# MIXR_Processing_-_STM32_NOR_Flash.net
KiCad netlist of a schematic drawn in Altium Designer
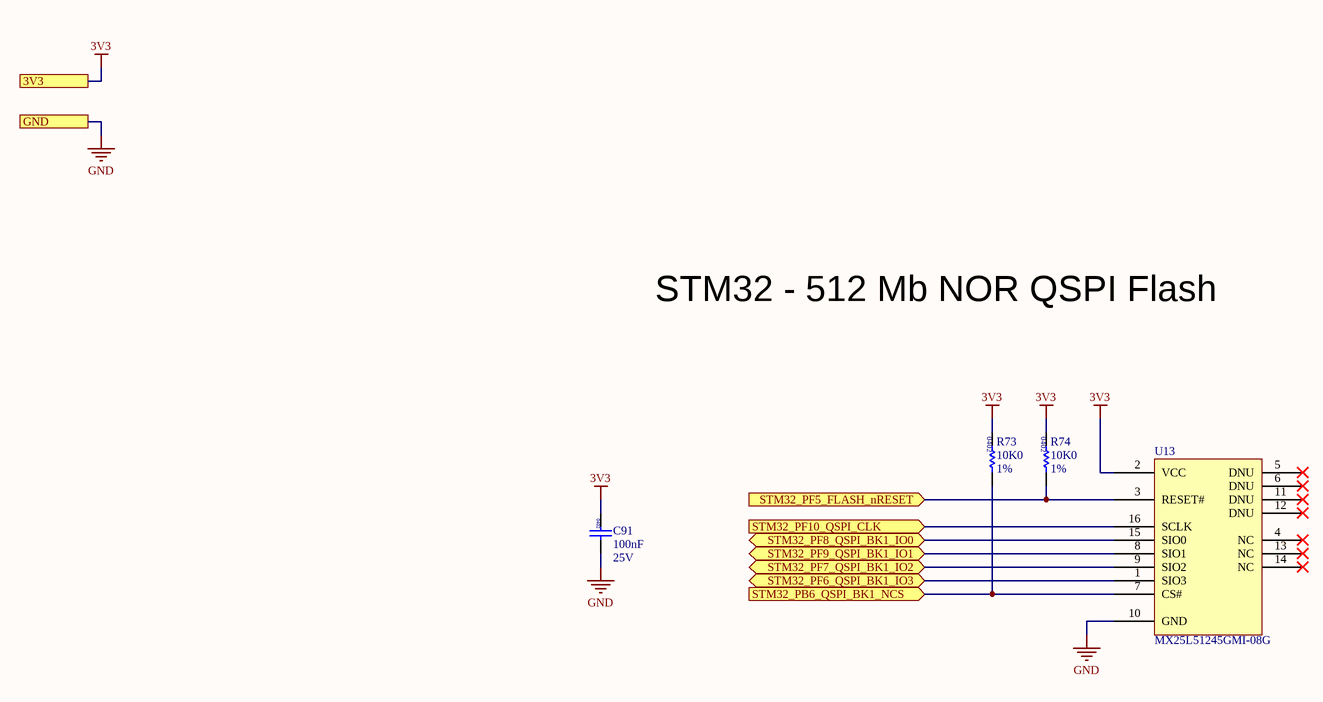
[diagram p0: MIXR Processing - STM32 NOR Flash.SchDoc]

(export (version "E")
  (design (tool "Eeschema 10.0.6"))
  (components
    (comp (ref "C91")
      (value "CAP CER 0.1UF 16V X7R 0402")
      (footprint "CAP 0402")
      (description "Cap Ceramic 0.1uF 25V X7R 10% SMD 0402 125C Paper T/R")
      (fields
        (field (name "TOLERANCE") "10%")
        (field (name "CAPACITANCE") "100nF")
        (field (name "VOLTAGE") "25V")
        (field (name "MANUFACTURER") "Murata")
      )
      (libsource (lib "Schematic Diagrams") (part "CAP CER 0.1UF 16V X7R 0402"))
    )
    (comp (ref "R73")
      (value "RES 10K OHM 1% 1/16W 0402")
      (footprint "RES 0402")
      (description "Surface Mount Thick Film Resistor, Rc Series, 10 Kohm, 62.5 Mw, - 1%, 50 V, 0402 [1005 Metric]")
      (fields
        (field (name "MANUFACTURER") "Yageo")
        (field (name "MANUFACTURER PART NUMBER") "RC0402FR-0710KL")
        (field (name "RESISTANCE") "10K0")
        (field (name "TOLERANCE") "1%")
      )
      (libsource (lib "Schematic Diagrams") (part "RES 10K OHM 1% 1/16W 0402"))
    )
    (comp (ref "R74")
      (value "RES 10K OHM 1% 1/16W 0402")
      (footprint "RES 0402")
      (description "Surface Mount Thick Film Resistor, Rc Series, 10 Kohm, 62.5 Mw, - 1%, 50 V, 0402 [1005 Metric]")
      (fields
        (field (name "MANUFACTURER") "Yageo")
        (field (name "MANUFACTURER PART NUMBER") "RC0402FR-0710KL")
        (field (name "RESISTANCE") "10K0")
        (field (name "TOLERANCE") "1%")
      )
      (libsource (lib "Schematic Diagrams") (part "RES 10K OHM 1% 1/16W 0402"))
    )
    (comp (ref "U13")
      (value "IC FLASH NOR 512Mb SPI 166MHz 16-SOP")
      (footprint "SOP127P1030X265-16N")
      (description "FLASH - NOR Memory IC 512Mb (64M x 8) SPI 166MHz 16-SOP")
      (fields
        (field (name "MANUFACTURER") "Macronix")
        (field (name "MANUFACTURER PART NUMBER") "MX25L51245GMI-08G")
      )
      (libsource (lib "Schematic Diagrams") (part "IC FLASH NOR 512Mb SPI 166MHz 16-SOP"))
    )
  )
  (nets
    (net (code "1") (name "/STM32_PB6_QSPI_BK1_NCS") (class "Default")
      (node (ref "R73") (pin "2") (pinfunction "2_2") (pintype "passive"))
      (node (ref "U13") (pin "7") (pinfunction "CS#_7") (pintype "passive"))
    )
    (net (code "2") (name "/STM32_PF5_FLASH_nRESET") (class "Default")
      (node (ref "R74") (pin "2") (pinfunction "2_2") (pintype "passive"))
      (node (ref "U13") (pin "3") (pinfunction "RESET#_3") (pintype "passive"))
    )
    (net (code "3") (name "/STM32_PF6_QSPI_BK1_IO3") (class "Default")
      (node (ref "U13") (pin "1") (pinfunction "SIO3_1") (pintype "passive"))
    )
    (net (code "4") (name "/STM32_PF7_QSPI_BK1_IO2") (class "Default")
      (node (ref "U13") (pin "9") (pinfunction "SIO2_9") (pintype "passive"))
    )
    (net (code "5") (name "/STM32_PF8_QSPI_BK1_IO0") (class "Default")
      (node (ref "U13") (pin "15") (pinfunction "SIO0_15") (pintype "passive"))
    )
    (net (code "6") (name "/STM32_PF9_QSPI_BK1_IO1") (class "Default")
      (node (ref "U13") (pin "8") (pinfunction "SIO1_8") (pintype "passive"))
    )
    (net (code "7") (name "/STM32_PF10_QSPI_CLK") (class "Default")
      (node (ref "U13") (pin "16") (pinfunction "SCLK_16") (pintype "passive"))
    )
    (net (code "8") (name "3V3") (class "Default")
      (node (ref "C91") (pin "1") (pinfunction "1_1") (pintype "passive"))
      (node (ref "R73") (pin "1") (pinfunction "1_1") (pintype "passive"))
      (node (ref "R74") (pin "1") (pinfunction "1_1") (pintype "passive"))
      (node (ref "U13") (pin "2") (pinfunction "VCC_2") (pintype "passive"))
    )
    (net (code "9") (name "GND") (class "Default")
      (node (ref "C91") (pin "2") (pinfunction "2_2") (pintype "passive"))
      (node (ref "U13") (pin "10") (pinfunction "GND_10") (pintype "passive"))
    )
    (net (code "10") (name "unconnected-(U13-DNU-Pad5)") (class "Default")
      (node (ref "U13") (pin "5") (pinfunction "DNU_5") (pintype "passive+no_connect"))
    )
    (net (code "11") (name "unconnected-(U13-DNU-Pad6)") (class "Default")
      (node (ref "U13") (pin "6") (pinfunction "DNU_6") (pintype "passive+no_connect"))
    )
    (net (code "12") (name "unconnected-(U13-DNU-Pad11)") (class "Default")
      (node (ref "U13") (pin "11") (pinfunction "DNU_11") (pintype "passive+no_connect"))
    )
    (net (code "13") (name "unconnected-(U13-DNU-Pad12)") (class "Default")
      (node (ref "U13") (pin "12") (pinfunction "DNU_12") (pintype "passive+no_connect"))
    )
    (net (code "14") (name "unconnected-(U13-NC-Pad4)") (class "Default")
      (node (ref "U13") (pin "4") (pinfunction "NC_4") (pintype "passive+no_connect"))
    )
    (net (code "15") (name "unconnected-(U13-NC-Pad13)") (class "Default")
      (node (ref "U13") (pin "13") (pinfunction "NC_13") (pintype "passive+no_connect"))
    )
    (net (code "16") (name "unconnected-(U13-NC-Pad14)") (class "Default")
      (node (ref "U13") (pin "14") (pinfunction "NC_14") (pintype "passive+no_connect"))
    )
  )
)
